# X100-7.net
KiCad netlist of a schematic drawn in EAGLE
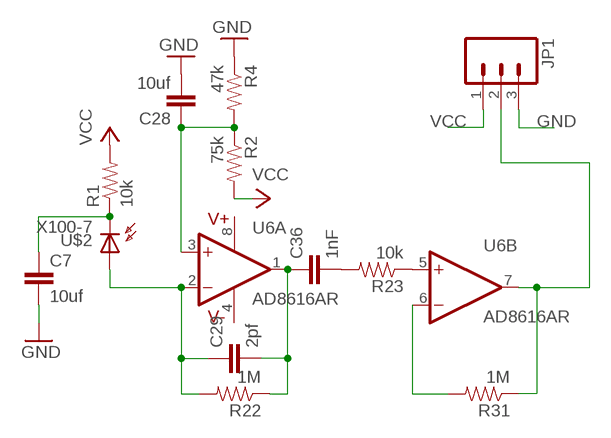
[diagram p0: schematic, sheet 1]

(export (version "E")
  (design (tool "Eeschema 10.0.6"))
  (components
    (comp (ref "C7")
      (value "10uf")
      (footprint "eagle-import:1206")
      (libsource (lib "eagle-import") (part "CAP1206"))
    )
    (comp (ref "C28")
      (value "10uf")
      (footprint "eagle-import:1206")
      (libsource (lib "eagle-import") (part "CAP1206"))
    )
    (comp (ref "C29")
      (value "2pf")
      (footprint "eagle-import:1206")
      (libsource (lib "eagle-import") (part "CAP1206"))
    )
    (comp (ref "C36")
      (value "1nF")
      (footprint "eagle-import:1206")
      (libsource (lib "eagle-import") (part "CAP1206"))
    )
    (comp (ref "JP1")
      (value "M03PTH")
      (footprint "eagle-import:1X03")
      (libsource (lib "eagle-import") (part "M03PTH"))
    )
    (comp (ref "R1")
      (value "10k")
      (footprint "eagle-import:1206")
      (libsource (lib "eagle-import") (part "RESISTOR1206"))
    )
    (comp (ref "R2")
      (value "75k")
      (footprint "eagle-import:1206")
      (libsource (lib "eagle-import") (part "RESISTOR1206"))
    )
    (comp (ref "R4")
      (value "47k")
      (footprint "eagle-import:1206")
      (libsource (lib "eagle-import") (part "RESISTOR1206"))
    )
    (comp (ref "R22")
      (value "1M")
      (footprint "eagle-import:1206")
      (libsource (lib "eagle-import") (part "RESISTOR1206"))
    )
    (comp (ref "R23")
      (value "10k")
      (footprint "eagle-import:1206")
      (libsource (lib "eagle-import") (part "RESISTOR1206"))
    )
    (comp (ref "R31")
      (value "1M")
      (footprint "eagle-import:1206")
      (libsource (lib "eagle-import") (part "RESISTOR1206"))
    )
    (comp (ref "U$2")
      (value "X100-7")
      (footprint "eagle-import:CERPIN")
      (libsource (lib "eagle-import") (part "X100-7"))
    )
    (comp (ref "U6")
      (value "AD8616AR")
      (footprint "eagle-import:SOIC8")
      (libsource (lib "eagle-import") (part "AD8616AR"))
    )
  )
  (nets
    (net (code "1") (name "/V+") (class "Default")
      (node (ref "U6") (pin "8") (pinfunction "V+_8") (pintype "power_in"))
    )
    (net (code "2") (name "/V-") (class "Default")
      (node (ref "U6") (pin "4") (pinfunction "V-_4") (pintype "power_in"))
    )
    (net (code "3") (name "GND") (class "Default")
      (node (ref "C28") (pin "2") (pinfunction "2_2") (pintype "passive"))
      (node (ref "C7") (pin "2") (pinfunction "2_2") (pintype "passive"))
      (node (ref "JP1") (pin "3") (pinfunction "3_3") (pintype "passive"))
      (node (ref "R4") (pin "1") (pinfunction "1_1") (pintype "passive"))
    )
    (net (code "4") (name "Net-(C7-Pad1)") (class "Default")
      (node (ref "C7") (pin "1") (pinfunction "1_1") (pintype "passive"))
      (node (ref "R1") (pin "1") (pinfunction "1_1") (pintype "passive"))
      (node (ref "U$2") (pin "2") (pinfunction "2_2") (pintype "passive"))
    )
    (net (code "5") (name "Net-(C36-Pad2)") (class "Default")
      (node (ref "C36") (pin "2") (pinfunction "2_2") (pintype "passive"))
      (node (ref "R23") (pin "2") (pinfunction "2_2") (pintype "passive"))
    )
    (net (code "6") (name "Net-(U6A-+IN)") (class "Default")
      (node (ref "C28") (pin "1") (pinfunction "1_1") (pintype "passive"))
      (node (ref "R2") (pin "1") (pinfunction "1_1") (pintype "passive"))
      (node (ref "R4") (pin "2") (pinfunction "2_2") (pintype "passive"))
      (node (ref "U6") (pin "3") (pinfunction "+IN_3") (pintype "input"))
    )
    (net (code "7") (name "Net-(U6A--IN)") (class "Default")
      (node (ref "C29") (pin "1") (pinfunction "1_1") (pintype "passive"))
      (node (ref "R22") (pin "2") (pinfunction "2_2") (pintype "passive"))
      (node (ref "U$2") (pin "1") (pinfunction "1_1") (pintype "passive"))
      (node (ref "U6") (pin "2") (pinfunction "-IN_2") (pintype "input"))
    )
    (net (code "8") (name "Net-(U6A-OUT)") (class "Default")
      (node (ref "C29") (pin "2") (pinfunction "2_2") (pintype "passive"))
      (node (ref "C36") (pin "1") (pinfunction "1_1") (pintype "passive"))
      (node (ref "R22") (pin "1") (pinfunction "1_1") (pintype "passive"))
      (node (ref "U6") (pin "1") (pinfunction "OUT_1") (pintype "output"))
    )
    (net (code "9") (name "Net-(U6B-+IN)") (class "Default")
      (node (ref "R23") (pin "1") (pinfunction "1_1") (pintype "passive"))
      (node (ref "U6") (pin "5") (pinfunction "+IN_5") (pintype "input"))
    )
    (net (code "10") (name "Net-(U6B--IN)") (class "Default")
      (node (ref "R31") (pin "2") (pinfunction "2_2") (pintype "passive"))
      (node (ref "U6") (pin "6") (pinfunction "-IN_6") (pintype "input"))
    )
    (net (code "11") (name "Net-(U6B-OUT)") (class "Default")
      (node (ref "JP1") (pin "2") (pinfunction "2_2") (pintype "passive"))
      (node (ref "R31") (pin "1") (pinfunction "1_1") (pintype "passive"))
      (node (ref "U6") (pin "7") (pinfunction "OUT_7") (pintype "output"))
    )
    (net (code "12") (name "VCC") (class "Default")
      (node (ref "JP1") (pin "1") (pinfunction "1_1") (pintype "passive"))
      (node (ref "R1") (pin "2") (pinfunction "2_2") (pintype "passive"))
      (node (ref "R2") (pin "2") (pinfunction "2_2") (pintype "passive"))
    )
  )
)
